# battery_pack.net
KiCad netlist of a schematic drawn in EAGLE
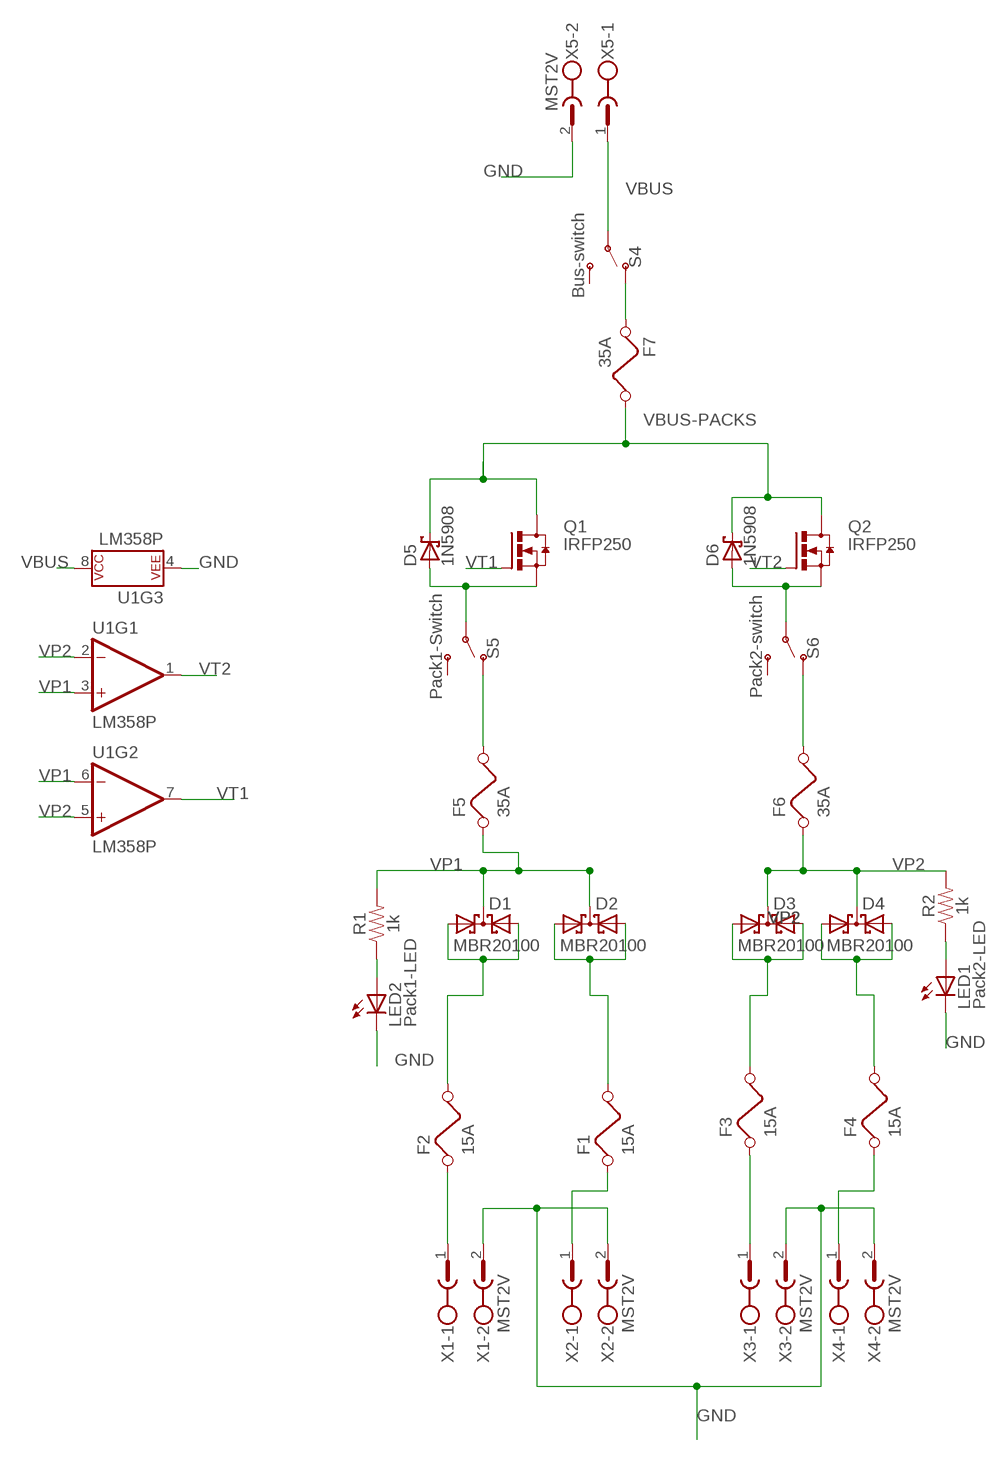
[diagram p0: schematic, sheet 1]

(export (version "E")
  (design (tool "Eeschema 10.0.6"))
  (components
    (comp (ref "D1")
      (value "MBR20100")
      (footprint "eagle-import:SOT82L")
      (libsource (lib "eagle-import") (part "DIODE_2SCHOTTKY-SOT82H"))
    )
    (comp (ref "D2")
      (value "MBR20100")
      (footprint "eagle-import:SOT82L")
      (libsource (lib "eagle-import") (part "DIODE_2SCHOTTKY-SOT82H"))
    )
    (comp (ref "D3")
      (value "MBR20100")
      (footprint "eagle-import:SOT82L")
      (libsource (lib "eagle-import") (part "DIODE_2SCHOTTKY-SOT82H"))
    )
    (comp (ref "D4")
      (value "MBR20100")
      (footprint "eagle-import:SOT82L")
      (libsource (lib "eagle-import") (part "DIODE_2SCHOTTKY-SOT82H"))
    )
    (comp (ref "D5")
      (value "1N5908")
      (footprint "eagle-import:C4111-15")
      (libsource (lib "eagle-import") (part "1N5908"))
    )
    (comp (ref "D6")
      (value "1N5908")
      (footprint "eagle-import:C4111-15")
      (libsource (lib "eagle-import") (part "1N5908"))
    )
    (comp (ref "F1")
      (value "15A")
      (footprint "eagle-import:FUSE")
      (libsource (lib "eagle-import") (part "FUSE"))
    )
    (comp (ref "F2")
      (value "15A")
      (footprint "eagle-import:FUSE")
      (libsource (lib "eagle-import") (part "FUSE"))
    )
    (comp (ref "F3")
      (value "15A")
      (footprint "eagle-import:FUSE")
      (libsource (lib "eagle-import") (part "FUSE"))
    )
    (comp (ref "F4")
      (value "15A")
      (footprint "eagle-import:FUSE")
      (libsource (lib "eagle-import") (part "FUSE"))
    )
    (comp (ref "F5")
      (value "35A")
      (footprint "eagle-import:FUSE")
      (libsource (lib "eagle-import") (part "FUSE"))
    )
    (comp (ref "F6")
      (value "35A")
      (footprint "eagle-import:FUSE")
      (libsource (lib "eagle-import") (part "FUSE"))
    )
    (comp (ref "F7")
      (value "35A")
      (footprint "eagle-import:FUSE")
      (libsource (lib "eagle-import") (part "FUSE"))
    )
    (comp (ref "LED1")
      (value "Pack2-LED")
      (footprint "eagle-import:Q62902-B156")
      (libsource (lib "eagle-import") (part "LEDB156"))
    )
    (comp (ref "LED2")
      (value "Pack1-LED")
      (footprint "eagle-import:Q62902-B156")
      (libsource (lib "eagle-import") (part "LEDB156"))
    )
    (comp (ref "Q1")
      (value "IRFP250")
      (footprint "eagle-import:TO-247AD-V")
      (libsource (lib "eagle-import") (part "IRFP250"))
    )
    (comp (ref "Q2")
      (value "IRFP250")
      (footprint "eagle-import:TO-247AD-V")
      (libsource (lib "eagle-import") (part "IRFP250"))
    )
    (comp (ref "R1")
      (value "1k")
      (footprint "eagle-import:AXIAL-0.4")
      (libsource (lib "eagle-import") (part "1KOHM"))
    )
    (comp (ref "R2")
      (value "1k")
      (footprint "eagle-import:AXIAL-0.4")
      (libsource (lib "eagle-import") (part "1KOHM"))
    )
    (comp (ref "S4")
      (value "Bus-switch")
      (footprint "eagle-import:SWITCH_SPDT_PTH_11.6X4.0MM_LOCK")
      (libsource (lib "eagle-import") (part "SWITCH-SPDT-PTH-11.6X4.0MM-LOCK"))
    )
    (comp (ref "S5")
      (value "Pack1-Switch")
      (footprint "eagle-import:SWITCH_SPDT_PTH_11.6X4.0MM_LOCK")
      (libsource (lib "eagle-import") (part "SWITCH-SPDT-PTH-11.6X4.0MM-LOCK"))
    )
    (comp (ref "S6")
      (value "Pack2-switch")
      (footprint "eagle-import:SWITCH_SPDT_PTH_11.6X4.0MM_LOCK")
      (libsource (lib "eagle-import") (part "SWITCH-SPDT-PTH-11.6X4.0MM-LOCK"))
    )
    (comp (ref "U1")
      (value "LM358P")
      (footprint "eagle-import:DIP08_LONGPAD")
      (libsource (lib "eagle-import") (part "LM358DIP08_LONGPAD"))
    )
    (comp (ref "X1")
      (value "MST2V")
      (footprint "eagle-import:MSTBV2")
      (libsource (lib "eagle-import") (part "MST2V"))
    )
    (comp (ref "X2")
      (value "MST2V")
      (footprint "eagle-import:MSTBV2")
      (libsource (lib "eagle-import") (part "MST2V"))
    )
    (comp (ref "X3")
      (value "MST2V")
      (footprint "eagle-import:MSTBV2")
      (libsource (lib "eagle-import") (part "MST2V"))
    )
    (comp (ref "X4")
      (value "MST2V")
      (footprint "eagle-import:MSTBV2")
      (libsource (lib "eagle-import") (part "MST2V"))
    )
    (comp (ref "X5")
      (value "MST2V")
      (footprint "eagle-import:MSTBV2")
      (libsource (lib "eagle-import") (part "con-phoenix-508_176_MST2V"))
    )
  )
  (nets
    (net (code "1") (name "/GND") (class "Default")
      (node (ref "LED1") (pin "K") (pinfunction "C_K") (pintype "passive"))
      (node (ref "LED2") (pin "K") (pinfunction "C_K") (pintype "passive"))
      (node (ref "U1") (pin "4") (pinfunction "P$V-_4") (pintype "bidirectional"))
      (node (ref "X1") (pin "2") (pinfunction "1_2") (pintype "passive"))
      (node (ref "X2") (pin "2") (pinfunction "1_2") (pintype "passive"))
      (node (ref "X3") (pin "2") (pinfunction "1_2") (pintype "passive"))
      (node (ref "X4") (pin "2") (pinfunction "1_2") (pintype "passive"))
      (node (ref "X5") (pin "2") (pinfunction "1_2") (pintype "passive"))
    )
    (net (code "2") (name "/VBUS") (class "Default")
      (node (ref "S4") (pin "2") (pinfunction "P_2") (pintype "passive"))
      (node (ref "U1") (pin "8") (pinfunction "P$V+_8") (pintype "bidirectional"))
      (node (ref "X5") (pin "1") (pinfunction "1_1") (pintype "passive"))
    )
    (net (code "3") (name "/VBUS-PACKS") (class "Default")
      (node (ref "D5") (pin "C") (pinfunction "C_C") (pintype "passive"))
      (node (ref "D6") (pin "C") (pinfunction "C_C") (pintype "passive"))
      (node (ref "F7") (pin "2") (pinfunction "2_2") (pintype "passive"))
      (node (ref "Q1") (pin "D") (pinfunction "D_D") (pintype "passive"))
      (node (ref "Q2") (pin "D") (pinfunction "D_D") (pintype "passive"))
    )
    (net (code "4") (name "/VP1") (class "Default")
      (node (ref "D1") (pin "C") (pinfunction "C_C") (pintype "passive"))
      (node (ref "D2") (pin "C") (pinfunction "C_C") (pintype "passive"))
      (node (ref "F5") (pin "1") (pinfunction "1_1") (pintype "passive"))
      (node (ref "R1") (pin "P$2") (pinfunction "2_P$2") (pintype "passive"))
      (node (ref "U1") (pin "3") (pinfunction "+IN_3") (pintype "input"))
      (node (ref "U1") (pin "6") (pinfunction "-IN_6") (pintype "input"))
    )
    (net (code "5") (name "/VP2") (class "Default")
      (node (ref "D3") (pin "C") (pinfunction "C_C") (pintype "passive"))
      (node (ref "D4") (pin "C") (pinfunction "C_C") (pintype "passive"))
      (node (ref "F6") (pin "1") (pinfunction "1_1") (pintype "passive"))
      (node (ref "R2") (pin "P$2") (pinfunction "2_P$2") (pintype "passive"))
      (node (ref "U1") (pin "2") (pinfunction "-IN_2") (pintype "input"))
      (node (ref "U1") (pin "5") (pinfunction "+IN_5") (pintype "input"))
    )
    (net (code "6") (name "/VT1") (class "Default")
      (node (ref "Q1") (pin "G") (pinfunction "G_G") (pintype "passive"))
      (node (ref "U1") (pin "7") (pinfunction "OUT_7") (pintype "output"))
    )
    (net (code "7") (name "/VT2") (class "Default")
      (node (ref "Q2") (pin "G") (pinfunction "G_G") (pintype "passive"))
      (node (ref "U1") (pin "1") (pinfunction "OUT_1") (pintype "output"))
    )
    (net (code "8") (name "Net-(D1-PadA1)") (class "Default")
      (node (ref "D1") (pin "A1") (pinfunction "A1_A1") (pintype "passive"))
      (node (ref "D1") (pin "A2") (pinfunction "A2_A2") (pintype "passive"))
      (node (ref "F2") (pin "2") (pinfunction "2_2") (pintype "passive"))
    )
    (net (code "9") (name "Net-(D2-PadA1)") (class "Default")
      (node (ref "D2") (pin "A1") (pinfunction "A1_A1") (pintype "passive"))
      (node (ref "D2") (pin "A2") (pinfunction "A2_A2") (pintype "passive"))
      (node (ref "F1") (pin "2") (pinfunction "2_2") (pintype "passive"))
    )
    (net (code "10") (name "Net-(D3-PadA1)") (class "Default")
      (node (ref "D3") (pin "A1") (pinfunction "A1_A1") (pintype "passive"))
      (node (ref "D3") (pin "A2") (pinfunction "A2_A2") (pintype "passive"))
      (node (ref "F3") (pin "2") (pinfunction "2_2") (pintype "passive"))
    )
    (net (code "11") (name "Net-(D4-PadA1)") (class "Default")
      (node (ref "D4") (pin "A1") (pinfunction "A1_A1") (pintype "passive"))
      (node (ref "D4") (pin "A2") (pinfunction "A2_A2") (pintype "passive"))
      (node (ref "F4") (pin "2") (pinfunction "2_2") (pintype "passive"))
    )
    (net (code "12") (name "Net-(F1-Pad1)") (class "Default")
      (node (ref "F1") (pin "1") (pinfunction "1_1") (pintype "passive"))
      (node (ref "X2") (pin "1") (pinfunction "1_1") (pintype "passive"))
    )
    (net (code "13") (name "Net-(F2-Pad1)") (class "Default")
      (node (ref "F2") (pin "1") (pinfunction "1_1") (pintype "passive"))
      (node (ref "X1") (pin "1") (pinfunction "1_1") (pintype "passive"))
    )
    (net (code "14") (name "Net-(F3-Pad1)") (class "Default")
      (node (ref "F3") (pin "1") (pinfunction "1_1") (pintype "passive"))
      (node (ref "X3") (pin "1") (pinfunction "1_1") (pintype "passive"))
    )
    (net (code "15") (name "Net-(F4-Pad1)") (class "Default")
      (node (ref "F4") (pin "1") (pinfunction "1_1") (pintype "passive"))
      (node (ref "X4") (pin "1") (pinfunction "1_1") (pintype "passive"))
    )
    (net (code "16") (name "Net-(R1-1)") (class "Default")
      (node (ref "LED2") (pin "A") (pinfunction "A_A") (pintype "passive"))
      (node (ref "R1") (pin "P$1") (pinfunction "1_P$1") (pintype "passive"))
    )
    (net (code "17") (name "Net-(R2-1)") (class "Default")
      (node (ref "LED1") (pin "A") (pinfunction "A_A") (pintype "passive"))
      (node (ref "R2") (pin "P$1") (pinfunction "1_P$1") (pintype "passive"))
    )
    (net (code "18") (name "Net-(S4-O)") (class "Default")
      (node (ref "F7") (pin "1") (pinfunction "1_1") (pintype "passive"))
      (node (ref "S4") (pin "1") (pinfunction "O_1") (pintype "passive"))
    )
    (net (code "19") (name "Net-(S5-O)") (class "Default")
      (node (ref "F5") (pin "2") (pinfunction "2_2") (pintype "passive"))
      (node (ref "S5") (pin "1") (pinfunction "O_1") (pintype "passive"))
    )
    (net (code "20") (name "Net-(S5-P)") (class "Default")
      (node (ref "D5") (pin "A") (pinfunction "A_A") (pintype "passive"))
      (node (ref "Q1") (pin "S") (pinfunction "S_S") (pintype "passive"))
      (node (ref "S5") (pin "2") (pinfunction "P_2") (pintype "passive"))
    )
    (net (code "21") (name "Net-(S6-O)") (class "Default")
      (node (ref "F6") (pin "2") (pinfunction "2_2") (pintype "passive"))
      (node (ref "S6") (pin "1") (pinfunction "O_1") (pintype "passive"))
    )
    (net (code "22") (name "Net-(S6-P)") (class "Default")
      (node (ref "D6") (pin "A") (pinfunction "A_A") (pintype "passive"))
      (node (ref "Q2") (pin "S") (pinfunction "S_S") (pintype "passive"))
      (node (ref "S6") (pin "2") (pinfunction "P_2") (pintype "passive"))
    )
    (net (code "23") (name "unconnected-(S4-S-Pad3)") (class "Default")
      (node (ref "S4") (pin "3") (pinfunction "S_3") (pintype "passive"))
    )
    (net (code "24") (name "unconnected-(S5-S-Pad3)") (class "Default")
      (node (ref "S5") (pin "3") (pinfunction "S_3") (pintype "passive"))
    )
    (net (code "25") (name "unconnected-(S6-S-Pad3)") (class "Default")
      (node (ref "S6") (pin "3") (pinfunction "S_3") (pintype "passive"))
    )
  )
)
